# 255SB_to_Switch_SMD.net
KiCad netlist of a schematic drawn in EAGLE
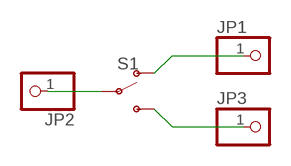
[diagram p0: schematic, sheet 1]

(export (version "E")
  (design (tool "Eeschema 10.0.6"))
  (components
    (comp (ref "JP1")
      (value "PINHD-1X01_2.54-SMD")
      (footprint "eagle-import:1X01SMD")
      (libsource (lib "eagle-import") (part "PINHD-1X01_2.54-SMD"))
    )
    (comp (ref "JP2")
      (value "PINHD-1X01_2.54-SMD")
      (footprint "eagle-import:1X01SMD")
      (libsource (lib "eagle-import") (part "PINHD-1X01_2.54-SMD"))
    )
    (comp (ref "JP3")
      (value "PINHD-1X01_2.54-SMD")
      (footprint "eagle-import:1X01SMD")
      (libsource (lib "eagle-import") (part "PINHD-1X01_2.54-SMD"))
    )
    (comp (ref "S1")
      (value "SWITCH-SPDT-SMD-AYZ0202")
      (footprint "eagle-import:SWITCH_DPDT_SMD_AYZ0202")
      (libsource (lib "eagle-import") (part "SWITCH-SPDT-SMD-AYZ0202"))
    )
  )
  (nets
    (net (code "1") (name "Net-(S1-O)") (class "Default")
      (node (ref "JP1") (pin "1") (pinfunction "1_1") (pintype "passive"))
      (node (ref "S1") (pin "1") (pinfunction "O_1") (pintype "passive"))
    )
    (net (code "2") (name "Net-(S1-P)") (class "Default")
      (node (ref "JP2") (pin "1") (pinfunction "1_1") (pintype "passive"))
      (node (ref "S1") (pin "2") (pinfunction "P_2") (pintype "passive"))
    )
    (net (code "3") (name "Net-(S1-S)") (class "Default")
      (node (ref "JP3") (pin "1") (pinfunction "1_1") (pintype "passive"))
      (node (ref "S1") (pin "3") (pinfunction "S_3") (pintype "passive"))
    )
  )
)
